# Shutdown_2019_v1_1_4.net
KiCad netlist of a schematic drawn in Altium Designer
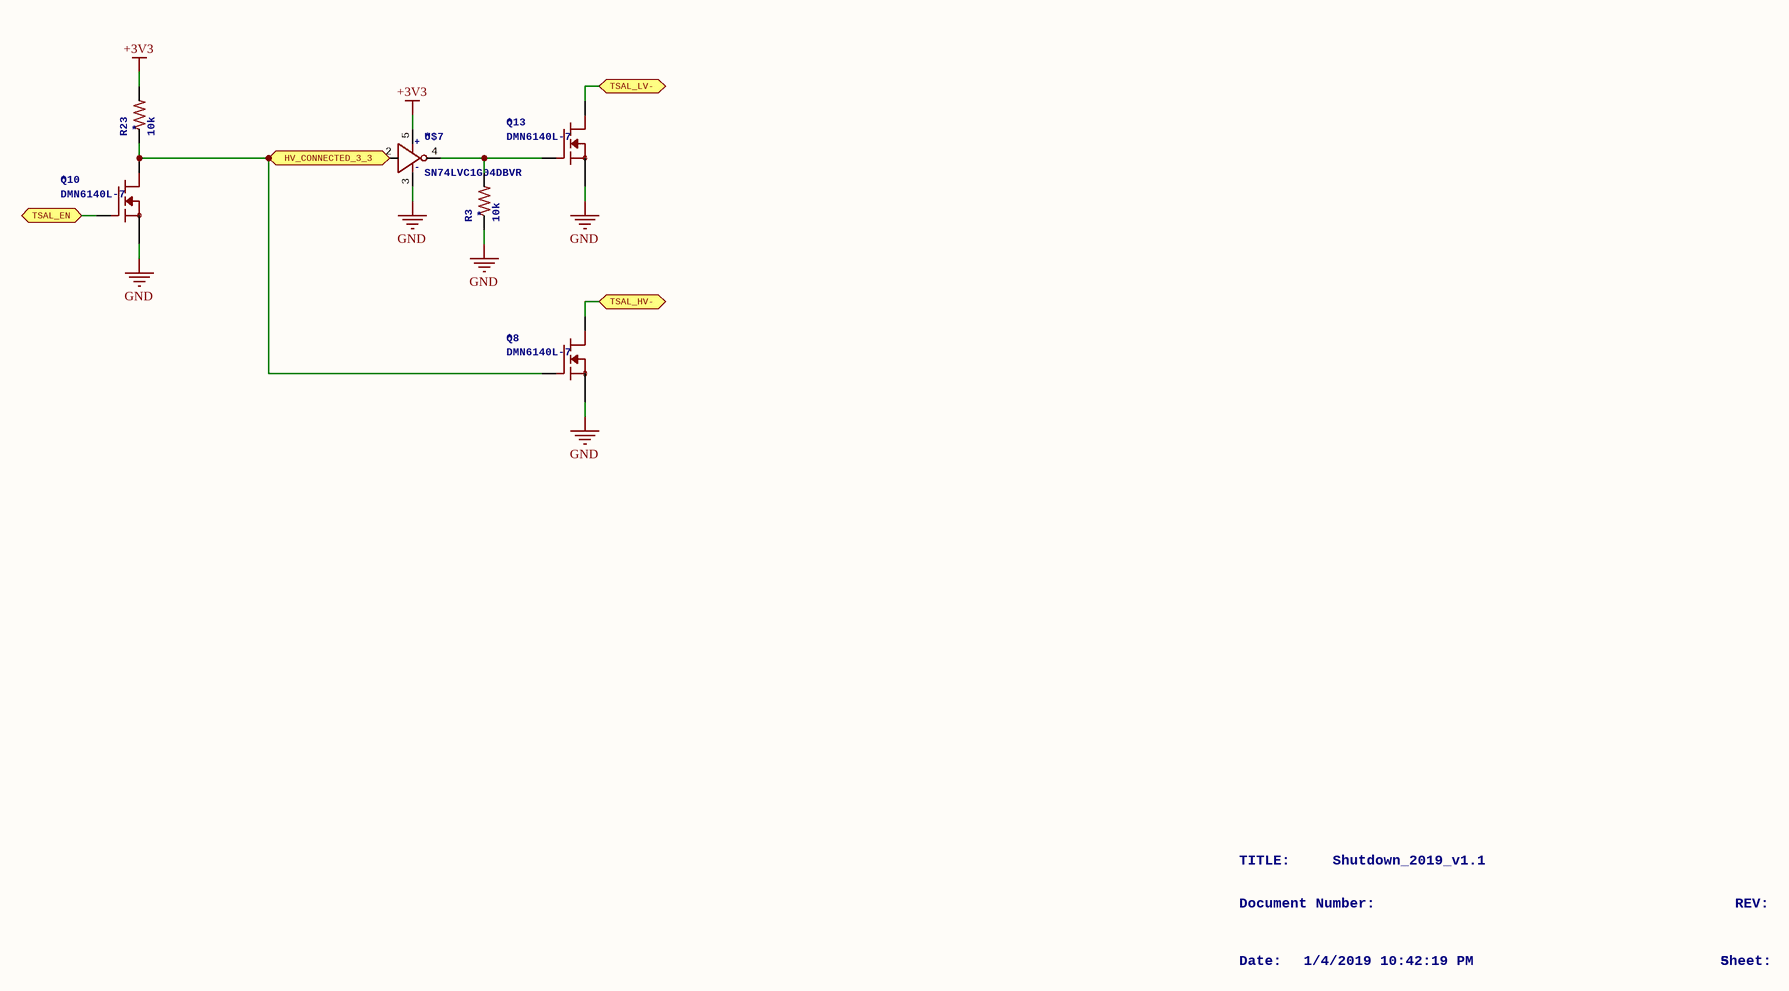
[diagram p0: Shutdown_2019_v1.1_4.SchDoc]

(export (version "E")
  (design (tool "Eeschema 10.0.6"))
  (components
    (comp (ref "Q8")
      (value "DMN6140L-7")
      (footprint "SOT23")
      (description "DMN6140L-7 Vgs(th) = 3V, Rds(on) = 140mOhm, Vds(max) = 60V")
      (fields (field (name "NAME") "*"))
      (libsource (lib "TRANS") (part "DMN6140L-7"))
    )
    (comp (ref "Q10")
      (value "DMN6140L-7")
      (footprint "SOT23")
      (description "DMN6140L-7 Vgs(th) = 3V, Rds(on) = 140mOhm, Vds(max) = 60V")
      (fields (field (name "NAME") "*"))
      (libsource (lib "TRANS") (part "DMN6140L-7"))
    )
    (comp (ref "Q13")
      (value "DMN6140L-7")
      (footprint "SOT23")
      (description "DMN6140L-7 Vgs(th) = 3V, Rds(on) = 140mOhm, Vds(max) = 60V")
      (fields (field (name "NAME") "*"))
      (libsource (lib "TRANS") (part "DMN6140L-7"))
    )
    (comp (ref "R3")
      (value "10k")
      (footprint "R0603")
      (description "RESISTOR, American symbol")
      (fields (field (name "NAME") "*"))
      (libsource (lib "resistor") (part "R-US_R0603"))
    )
    (comp (ref "R23")
      (value "10k")
      (footprint "R0603")
      (description "RESISTOR, American symbol")
      (fields (field (name "NAME") "*"))
      (libsource (lib "resistor") (part "R-US_R0603"))
    )
    (comp (ref "U$7")
      (value "SN74LVC1G04DBVR")
      (footprint "SOT23-5L")
      (description "TI Single Chip InverterSN74LVC1G04DBVRhttp://www.ti.com/lit/ds/symlink/sn74lvc1g04.pdf")
      (fields (field (name "NAME") "*") (field (name "+") "+") (field (name "-") "-"))
      (libsource (lib "Display_Custom") (part "SN74LVC1G04DBVR"))
    )
  )
  (nets
    (net (code "1") (name "+3V3") (class "Default")
      (node (ref "R23") (pin "2") (pinfunction "2_2") (pintype "passive"))
      (node (ref "U$7") (pin "5") (pinfunction "V+_5") (pintype "passive"))
    )
    (net (code "2") (name "/HV_CONNECTED_3_3") (class "Default")
      (node (ref "Q10") (pin "3") (pinfunction "D_3") (pintype "passive"))
      (node (ref "Q8") (pin "1") (pinfunction "G_1") (pintype "passive"))
      (node (ref "R23") (pin "1") (pinfunction "1_1") (pintype "passive"))
      (node (ref "U$7") (pin "2") (pinfunction "A_2") (pintype "passive"))
    )
    (net (code "3") (name "/TSAL_EN") (class "Default")
      (node (ref "Q10") (pin "1") (pinfunction "G_1") (pintype "passive"))
    )
    (net (code "4") (name "/TSAL_HV-") (class "Default")
      (node (ref "Q8") (pin "3") (pinfunction "D_3") (pintype "passive"))
    )
    (net (code "5") (name "/TSAL_LV-") (class "Default")
      (node (ref "Q13") (pin "3") (pinfunction "D_3") (pintype "passive"))
    )
    (net (code "6") (name "GND") (class "Default")
      (node (ref "Q10") (pin "2") (pinfunction "S_2") (pintype "passive"))
      (node (ref "Q13") (pin "2") (pinfunction "S_2") (pintype "passive"))
      (node (ref "Q8") (pin "2") (pinfunction "S_2") (pintype "passive"))
      (node (ref "R3") (pin "1") (pinfunction "1_1") (pintype "passive"))
      (node (ref "U$7") (pin "3") (pinfunction "GND_3") (pintype "passive"))
    )
    (net (code "7") (name "Net-(Q13-G)") (class "Default")
      (node (ref "Q13") (pin "1") (pinfunction "G_1") (pintype "passive"))
      (node (ref "R3") (pin "2") (pinfunction "2_2") (pintype "passive"))
      (node (ref "U$7") (pin "4") (pinfunction "Y_4") (pintype "passive"))
    )
  )
)
